# 02_boost3v3D.net
KiCad netlist of a schematic drawn in Altium Designer
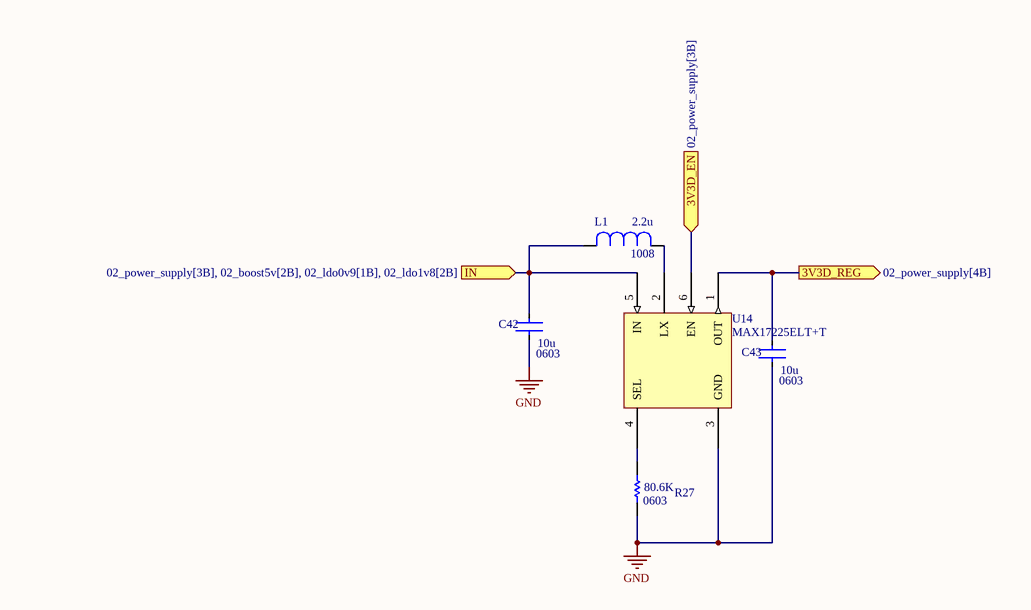
[diagram p0: 02_boost3v3D.SchDoc]

(export (version "E")
  (design (tool "Eeschema 10.0.6"))
  (components
    (comp (ref "C42")
      (value "C1608X5R1A106K080AC")
      (footprint "CAPTDK0603")
      (description "CAP CER 10UF 10V X5R 0603")
      (libsource (lib "tcspc00") (part "C1608X5R1A106K080AC"))
    )
    (comp (ref "C43")
      (value "C1608X5R1A106K080AC")
      (footprint "CAPTDK0603")
      (description "CAP CER 10UF 10V X5R 0603")
      (libsource (lib "tcspc00") (part "C1608X5R1A106K080AC"))
    )
    (comp (ref "L1")
      (value "DFE252012P-2R2M=P2")
      (footprint "INDMURT1008")
      (description "FIXED IND 2.2UH 2.2A 84 MOHM SMD")
      (fields (field (name "COPYRIGHT") "Copyright (C) 2022 Ultra Librarian. All rights reserved."))
      (libsource (lib "tcspc00") (part "DFE252012P-2R2M=P2"))
    )
    (comp (ref "R27")
      (value "RMCF0603FT80K6")
      (footprint "RES-STACK-POLE-0603")
      (description "RES 80.6K OHM 1% 1/10W 0603")
      (fields (field (name "COPYRIGHT") "Copyright (C) 2022 Ultra Librarian. All rights reserved."))
      (libsource (lib "tcspc00") (part "RMCF0603FT80K6"))
    )
    (comp (ref "U14")
      (value "MAX17225ELT+T")
      (footprint "MAX17222ELT+T")
      (description "IC REG 0.9V TO 5V 1A 6UDFN")
      (fields (field (name "COPYRIGHT") "Copyright (C) 2022 Ultra Librarian. All rights reserved."))
      (libsource (lib "tcspc00") (part "MAX17225ELT+T"))
    )
  )
  (nets
    (net (code "1") (name "/3V3D_EN") (class "Default")
      (node (ref "U14") (pin "6") (pinfunction "EN_6") (pintype "input"))
    )
    (net (code "2") (name "/3V3D_REG") (class "Default")
      (node (ref "C43") (pin "1") (pinfunction "1_1") (pintype "passive"))
      (node (ref "U14") (pin "1") (pinfunction "OUT_1") (pintype "output"))
    )
    (net (code "3") (name "/IN") (class "Default")
      (node (ref "C42") (pin "1") (pinfunction "1_1") (pintype "passive"))
      (node (ref "L1") (pin "2") (pinfunction "2_2") (pintype "passive"))
      (node (ref "U14") (pin "5") (pinfunction "IN_5") (pintype "input"))
    )
    (net (code "4") (name "GND") (class "Default")
      (node (ref "C42") (pin "2") (pinfunction "2_2") (pintype "passive"))
      (node (ref "C43") (pin "2") (pinfunction "2_2") (pintype "passive"))
      (node (ref "R27") (pin "1") (pinfunction "1_1") (pintype "passive"))
      (node (ref "U14") (pin "3") (pinfunction "GND_3") (pintype "passive"))
    )
    (net (code "5") (name "Net-(U14-LX)") (class "Default")
      (node (ref "L1") (pin "1") (pinfunction "1_1") (pintype "passive"))
      (node (ref "U14") (pin "2") (pinfunction "LX_2") (pintype "passive"))
    )
    (net (code "6") (name "Net-(U14-SEL)") (class "Default")
      (node (ref "R27") (pin "2") (pinfunction "2_2") (pintype "passive"))
      (node (ref "U14") (pin "4") (pinfunction "SEL_4") (pintype "passive"))
    )
  )
)
